# standard_jig.net
KiCad netlist of a schematic drawn in EAGLE
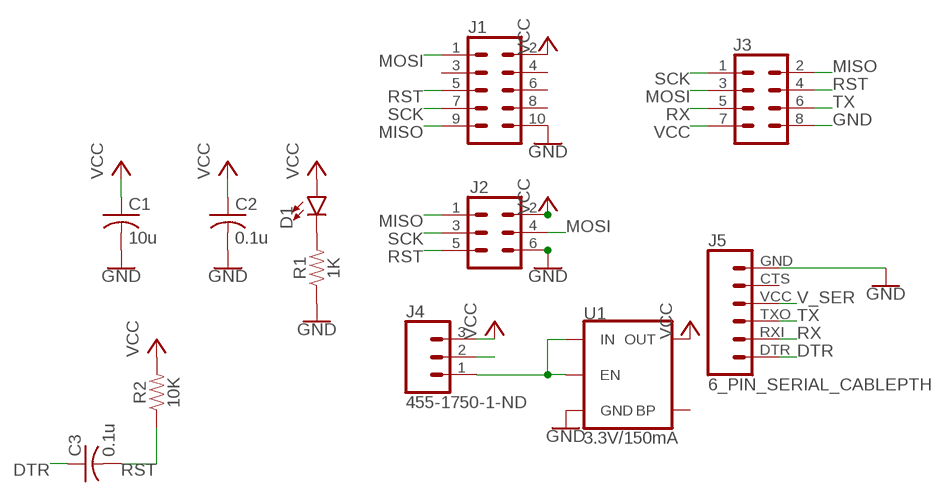
[diagram p0: schematic, sheet 1]

(export (version "E")
  (design (tool "Eeschema 10.0.6"))
  (components
    (comp (ref "C1")
      (value "10u")
      (footprint "eagle-import:C1206")
      (libsource (lib "eagle-import") (part "C-USC1206"))
    )
    (comp (ref "C2")
      (value "0.1u")
      (footprint "eagle-import:C1206")
      (libsource (lib "eagle-import") (part "C-USC1206"))
    )
    (comp (ref "C3")
      (value "0.1u")
      (footprint "eagle-import:C1206")
      (libsource (lib "eagle-import") (part "C-USC1206"))
    )
    (comp (ref "D1")
      (value "LED1206")
      (footprint "eagle-import:LED-1206")
      (libsource (lib "eagle-import") (part "LED1206"))
    )
    (comp (ref "J1")
      (value "CONN_05X2SHD")
      (footprint "eagle-import:2X5-SHROUDED")
      (libsource (lib "eagle-import") (part "CONN_05X2SHD"))
    )
    (comp (ref "J2")
      (value "CONN_03X2SHROUD")
      (footprint "eagle-import:2X3-SHROUDED")
      (libsource (lib "eagle-import") (part "CONN_03X2SHROUD"))
    )
    (comp (ref "J3")
      (value "CONN_04X2")
      (footprint "eagle-import:2X4")
      (libsource (lib "eagle-import") (part "CONN_04X2"))
    )
    (comp (ref "J4")
      (value "455-1750-1-ND")
      (footprint "eagle-import:1X03")
      (libsource (lib "eagle-import") (part "CONN_03"))
    )
    (comp (ref "J5")
      (value "6_PIN_SERIAL_CABLEPTH")
      (footprint "eagle-import:FTDI_BASIC")
      (libsource (lib "eagle-import") (part "6_PIN_SERIAL_CABLEPTH"))
    )
    (comp (ref "R1")
      (value "1K")
      (footprint "eagle-import:1206")
      (libsource (lib "eagle-import") (part "RESISTOR1206"))
    )
    (comp (ref "R2")
      (value "10K")
      (footprint "eagle-import:1206")
      (libsource (lib "eagle-import") (part "RESISTOR1206"))
    )
    (comp (ref "U1")
      (value "3.3V/150mA")
      (footprint "eagle-import:SOT23-5")
      (libsource (lib "eagle-import") (part "V_REG_MIC52053.3V"))
    )
  )
  (nets
    (net (code "1") (name "/DTR") (class "Default")
      (node (ref "C3") (pin "1") (pinfunction "1_1") (pintype "passive"))
      (node (ref "J5") (pin "DTR") (pinfunction "1_DTR") (pintype "passive"))
    )
    (net (code "2") (name "/MISO") (class "Default")
      (node (ref "J1") (pin "9") (pinfunction "9_9") (pintype "passive"))
      (node (ref "J2") (pin "1") (pinfunction "1_1") (pintype "bidirectional"))
      (node (ref "J3") (pin "2") (pinfunction "2_2") (pintype "passive"))
    )
    (net (code "3") (name "/MOSI") (class "Default")
      (node (ref "J1") (pin "1") (pinfunction "1_1") (pintype "passive"))
      (node (ref "J2") (pin "4") (pinfunction "4_4") (pintype "bidirectional"))
      (node (ref "J3") (pin "3") (pinfunction "3_3") (pintype "passive"))
    )
    (net (code "4") (name "/RST") (class "Default")
      (node (ref "C3") (pin "2") (pinfunction "2_2") (pintype "passive"))
      (node (ref "J1") (pin "5") (pinfunction "5_5") (pintype "passive"))
      (node (ref "J2") (pin "5") (pinfunction "5_5") (pintype "bidirectional"))
      (node (ref "J3") (pin "4") (pinfunction "4_4") (pintype "passive"))
      (node (ref "R2") (pin "1") (pinfunction "1_1") (pintype "passive"))
    )
    (net (code "5") (name "/RX") (class "Default")
      (node (ref "J3") (pin "5") (pinfunction "5_5") (pintype "passive"))
      (node (ref "J5") (pin "RXI") (pinfunction "2_RXI") (pintype "passive"))
    )
    (net (code "6") (name "/SCK") (class "Default")
      (node (ref "J1") (pin "7") (pinfunction "7_7") (pintype "passive"))
      (node (ref "J2") (pin "3") (pinfunction "3_3") (pintype "bidirectional"))
      (node (ref "J3") (pin "1") (pinfunction "1_1") (pintype "passive"))
    )
    (net (code "7") (name "/TX") (class "Default")
      (node (ref "J3") (pin "6") (pinfunction "6_6") (pintype "passive"))
      (node (ref "J5") (pin "TXO") (pinfunction "3_TXO") (pintype "passive"))
    )
    (net (code "8") (name "/V_SER") (class "Default")
      (node (ref "J5") (pin "VCC") (pinfunction "4_VCC") (pintype "passive"))
    )
    (net (code "9") (name "GND") (class "Default")
      (node (ref "C1") (pin "2") (pinfunction "2_2") (pintype "passive"))
      (node (ref "C2") (pin "2") (pinfunction "2_2") (pintype "passive"))
      (node (ref "J1") (pin "10") (pinfunction "10_10") (pintype "passive"))
      (node (ref "J2") (pin "6") (pinfunction "6_6") (pintype "bidirectional"))
      (node (ref "J3") (pin "8") (pinfunction "8_8") (pintype "passive"))
      (node (ref "J5") (pin "GND") (pinfunction "6_GND") (pintype "passive"))
      (node (ref "R1") (pin "1") (pinfunction "1_1") (pintype "passive"))
      (node (ref "U1") (pin "2") (pinfunction "GND_2") (pintype "input"))
    )
    (net (code "10") (name "Net-(D1-PadC)") (class "Default")
      (node (ref "D1") (pin "C") (pinfunction "C_C") (pintype "passive"))
      (node (ref "R1") (pin "2") (pinfunction "2_2") (pintype "passive"))
    )
    (net (code "11") (name "Net-(U1-EN)") (class "Default")
      (node (ref "J4") (pin "1") (pinfunction "1_1") (pintype "passive"))
      (node (ref "U1") (pin "1") (pinfunction "IN_1") (pintype "input"))
      (node (ref "U1") (pin "3") (pinfunction "EN_3") (pintype "input"))
    )
    (net (code "12") (name "VCC") (class "Default")
      (node (ref "C1") (pin "1") (pinfunction "1_1") (pintype "passive"))
      (node (ref "C2") (pin "1") (pinfunction "1_1") (pintype "passive"))
      (node (ref "D1") (pin "A") (pinfunction "A_A") (pintype "passive"))
      (node (ref "J1") (pin "2") (pinfunction "2_2") (pintype "passive"))
      (node (ref "J2") (pin "2") (pinfunction "2_2") (pintype "bidirectional"))
      (node (ref "J3") (pin "7") (pinfunction "7_7") (pintype "passive"))
      (node (ref "J4") (pin "3") (pinfunction "3_3") (pintype "passive"))
      (node (ref "R2") (pin "2") (pinfunction "2_2") (pintype "passive"))
      (node (ref "U1") (pin "5") (pinfunction "OUT_5") (pintype "passive"))
    )
    (net (code "13") (name "unconnected-(J1-Pad3)") (class "Default")
      (node (ref "J1") (pin "3") (pinfunction "3_3") (pintype "passive"))
    )
    (net (code "14") (name "unconnected-(J1-Pad4)") (class "Default")
      (node (ref "J1") (pin "4") (pinfunction "4_4") (pintype "passive"))
    )
    (net (code "15") (name "unconnected-(J1-Pad6)") (class "Default")
      (node (ref "J1") (pin "6") (pinfunction "6_6") (pintype "passive"))
    )
    (net (code "16") (name "unconnected-(J1-Pad8)") (class "Default")
      (node (ref "J1") (pin "8") (pinfunction "8_8") (pintype "passive"))
    )
    (net (code "17") (name "unconnected-(J4-Pad2)") (class "Default")
      (node (ref "J4") (pin "2") (pinfunction "2_2") (pintype "passive"))
    )
    (net (code "18") (name "unconnected-(J5-5-PadCTS)") (class "Default")
      (node (ref "J5") (pin "CTS") (pinfunction "5_CTS") (pintype "passive"))
    )
    (net (code "19") (name "unconnected-(U1-BP-Pad4)") (class "Default")
      (node (ref "U1") (pin "4") (pinfunction "BP_4") (pintype "input"))
    )
  )
)
